# Spar7_rebuild.net
KiCad netlist of a schematic drawn in EAGLE
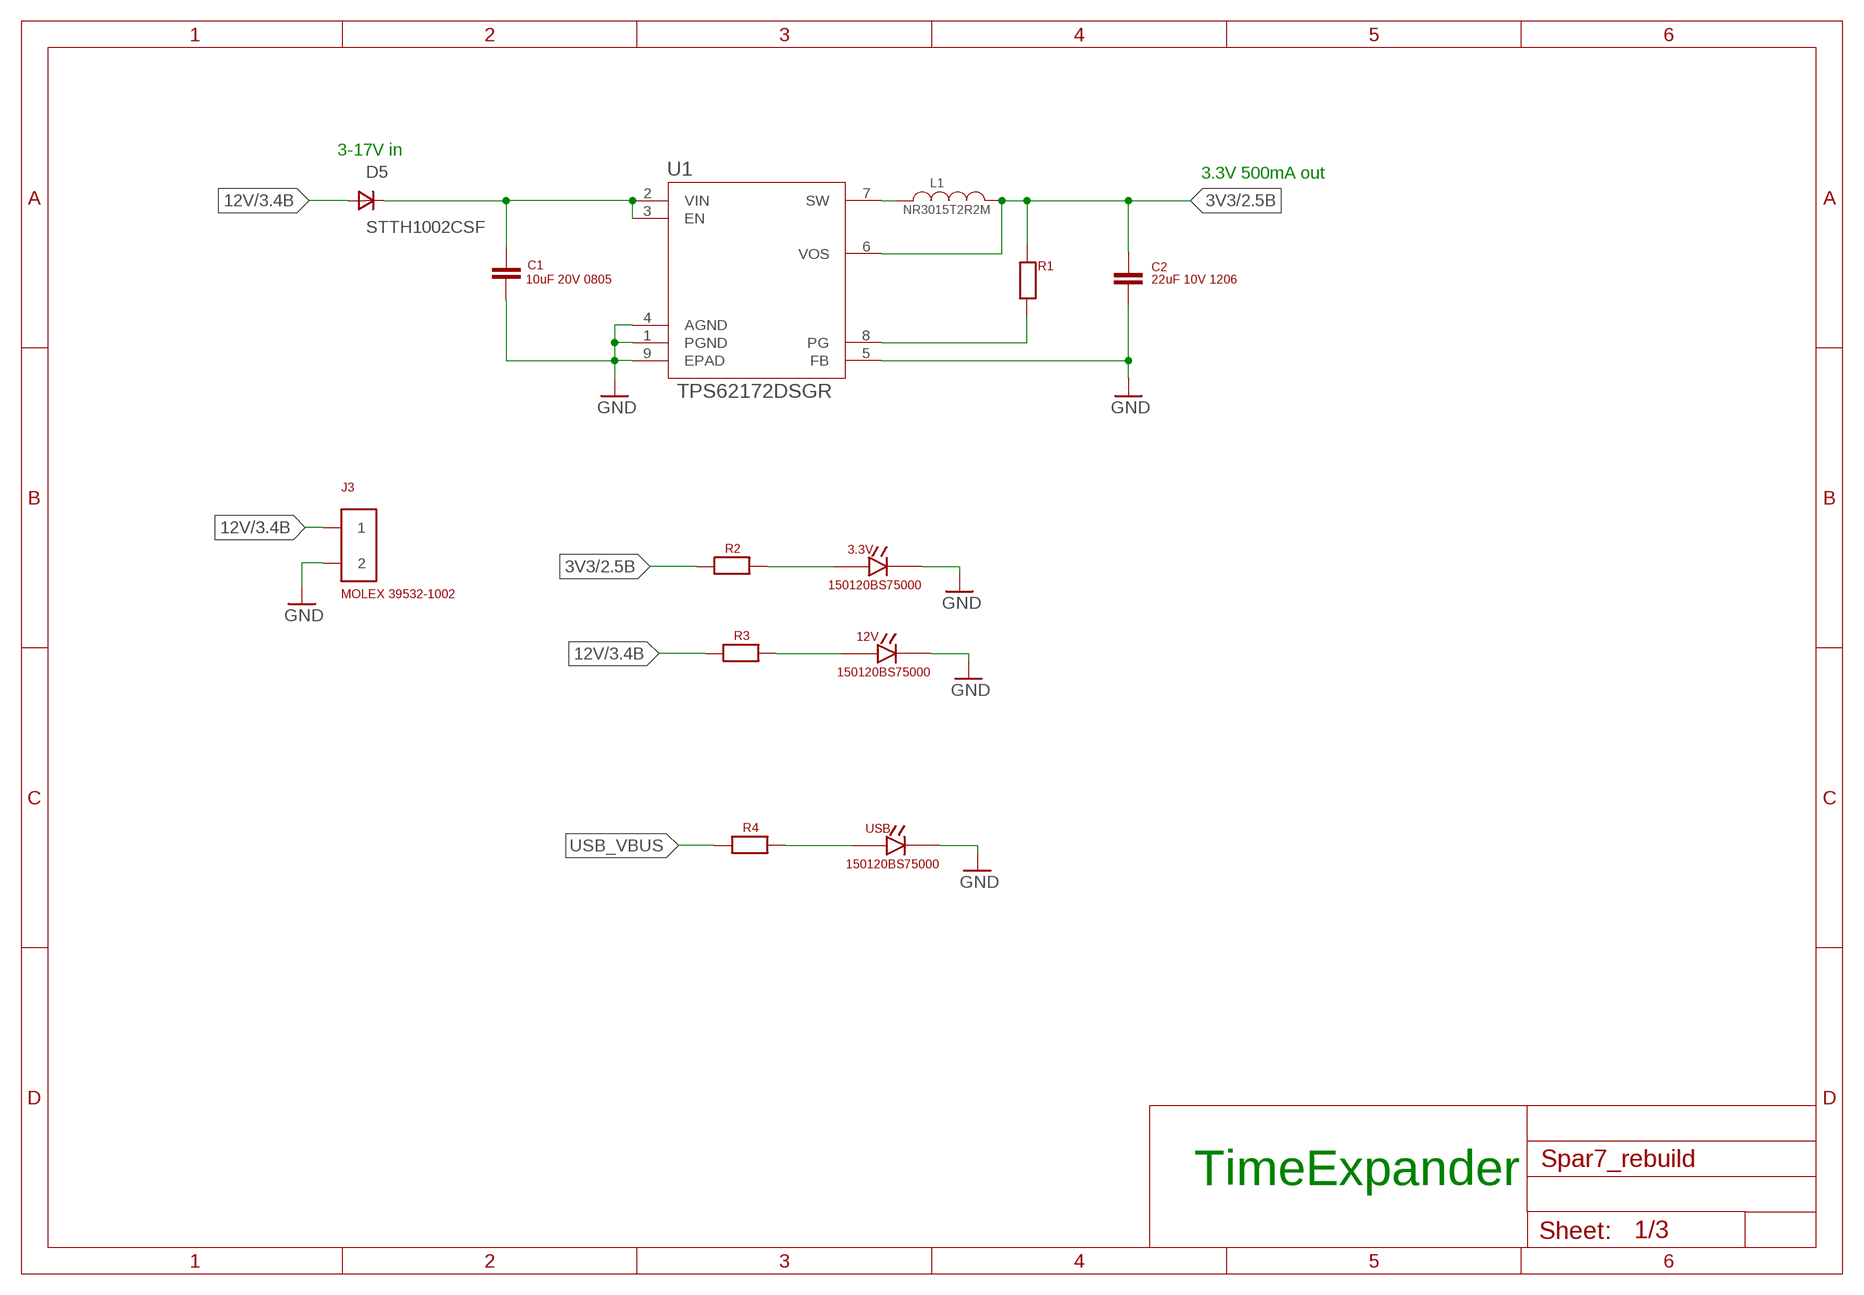
[diagram p0: schematic, sheet 1]
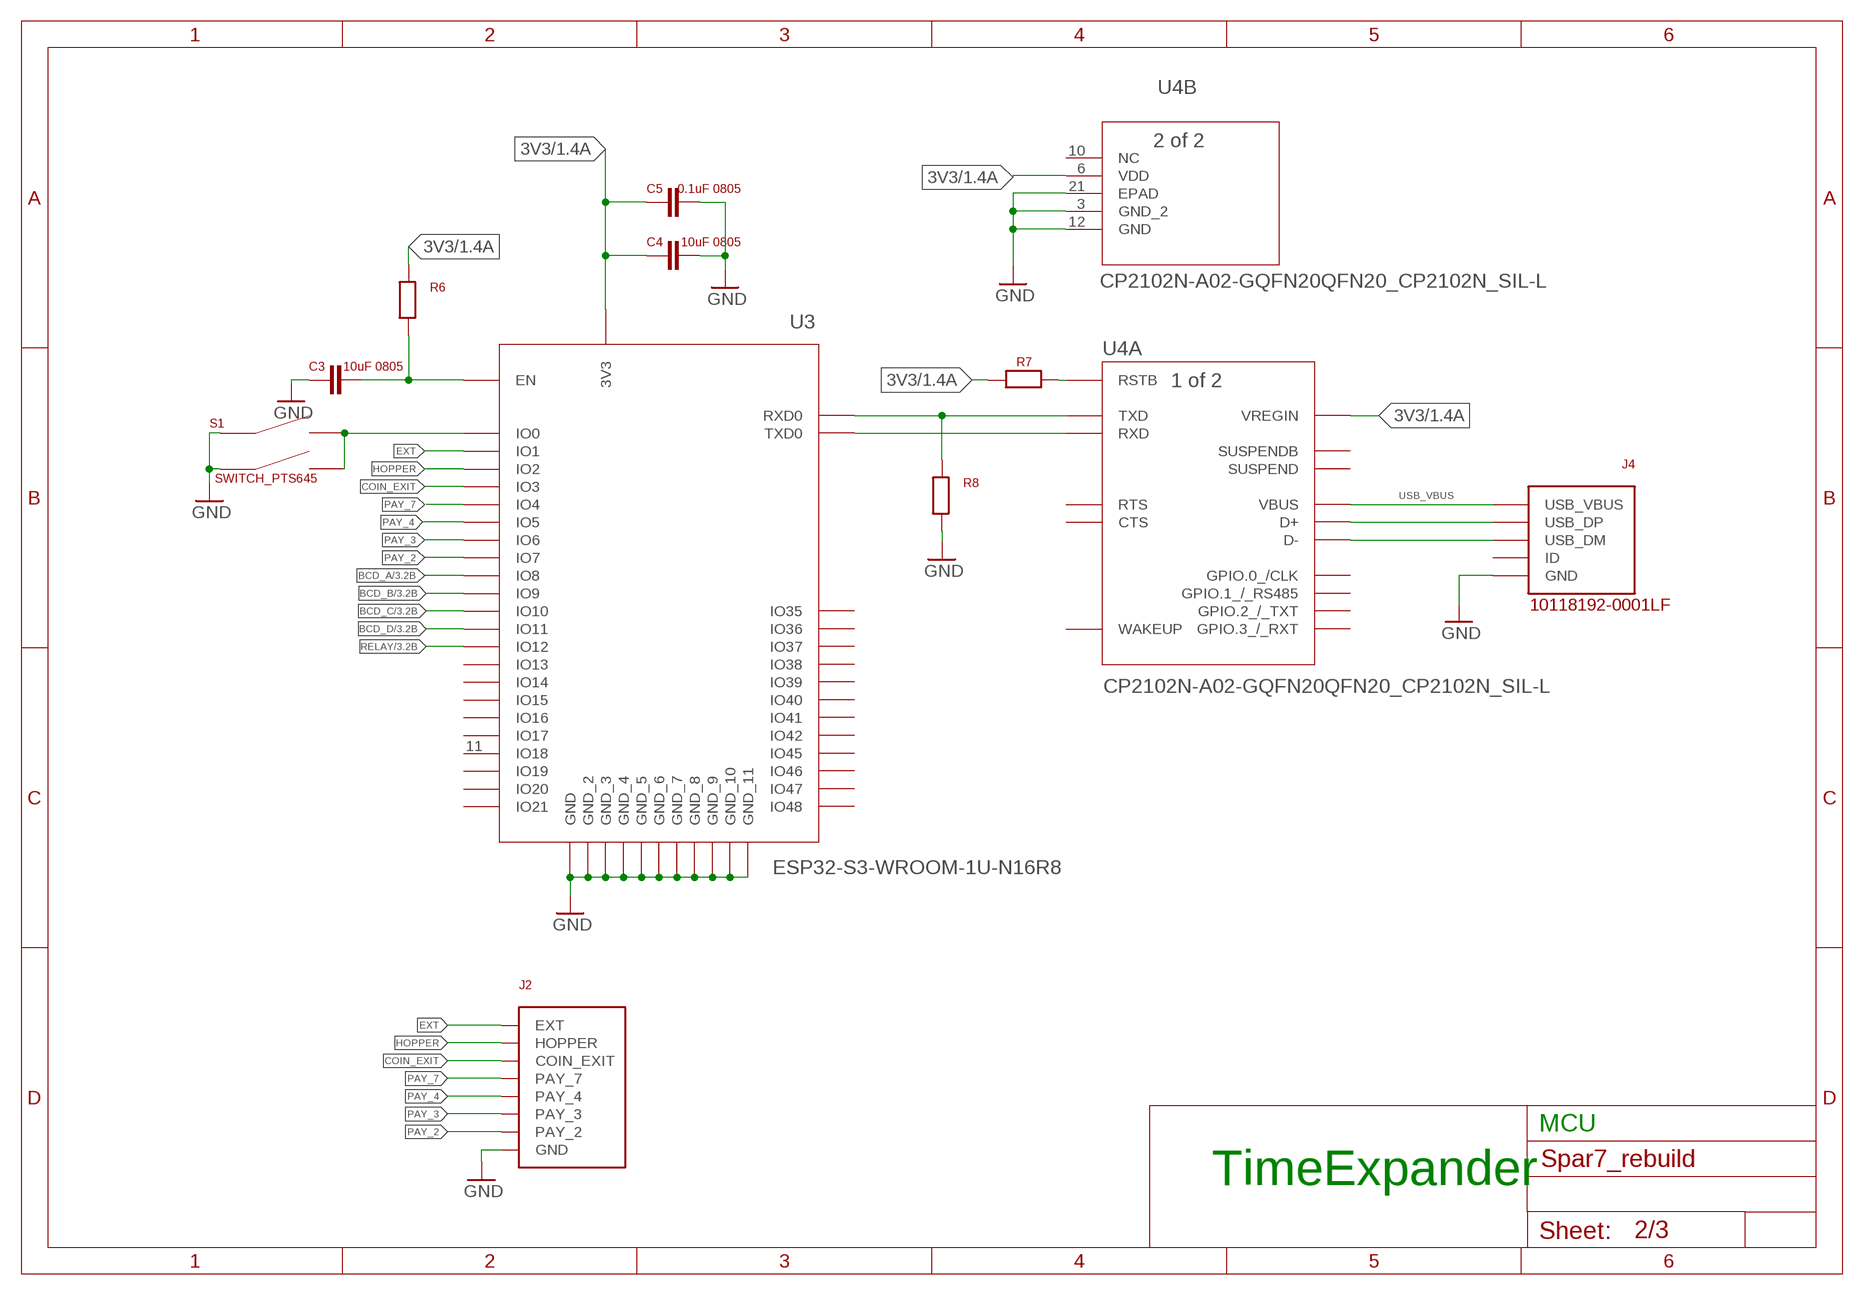
[diagram p1: schematic, sheet 2]
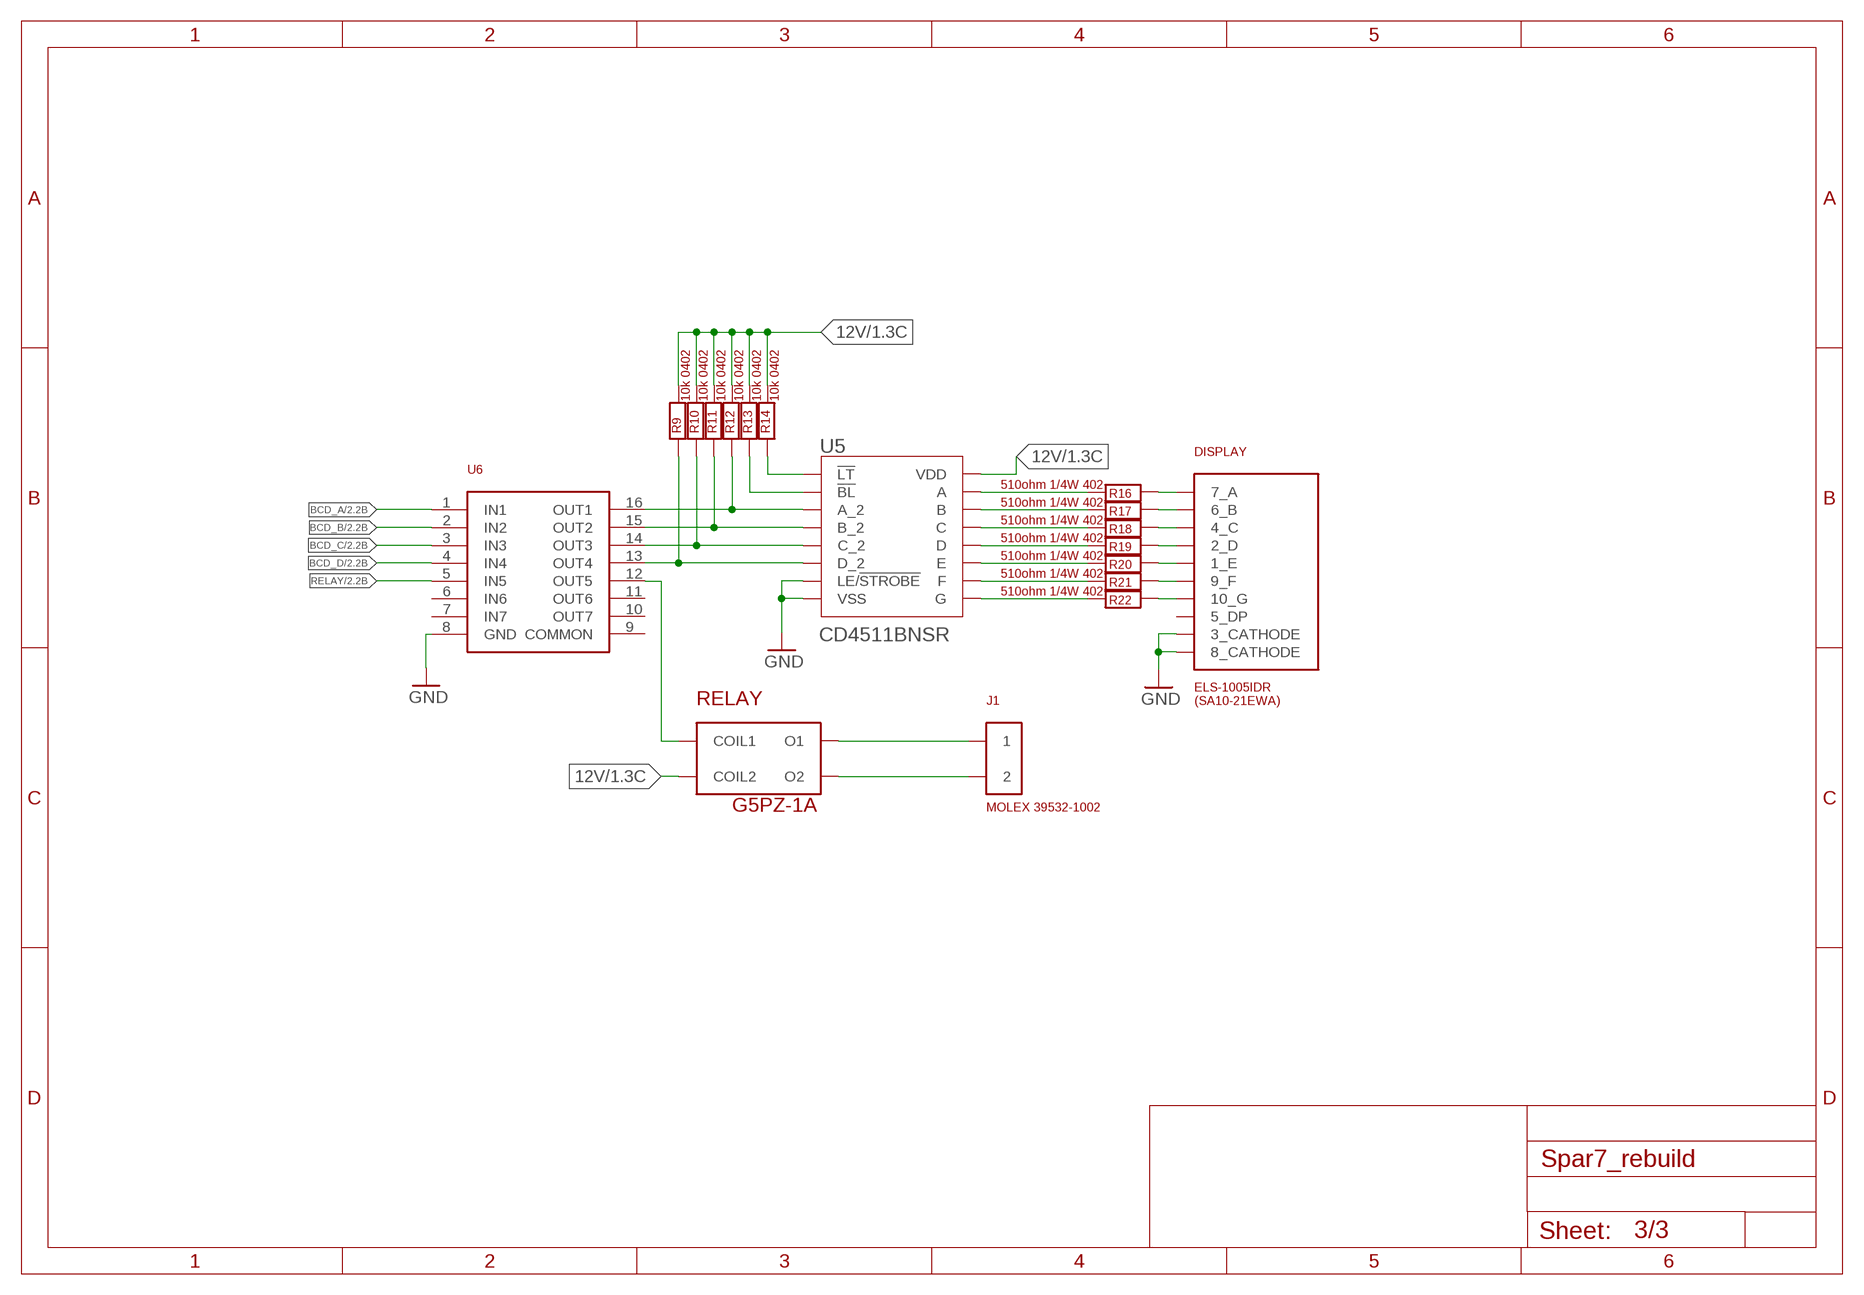
[diagram p2: schematic, sheet 3]

(export (version "E")
  (design (tool "Eeschema 10.0.6"))
  (components
    (comp (ref "DISPLAY")
      (value "ELS-1005IDR-SA10-21EWA")
      (footprint "eagle-import:ELS-1005IDR-SA10-21EWA")
      (libsource (lib "eagle-import") (part "ELS-1005IDR-SA10-21EWA"))
    )
    (comp (ref "J1")
      (value "MOLEX-39532-1002")
      (footprint "eagle-import:MOLEX-39532-1002")
      (libsource (lib "eagle-import") (part "MOLEX-39532-1002"))
    )
    (comp (ref "R9")
      (value "10k 0402")
      (footprint "eagle-import:RES_0402")
      (libsource (lib "eagle-import") (part "RESISTOR0402"))
    )
    (comp (ref "R10")
      (value "10k 0402")
      (footprint "eagle-import:RES_0402")
      (libsource (lib "eagle-import") (part "RESISTOR0402"))
    )
    (comp (ref "R11")
      (value "10k 0402")
      (footprint "eagle-import:RES_0402")
      (libsource (lib "eagle-import") (part "RESISTOR0402"))
    )
    (comp (ref "R12")
      (value "10k 0402")
      (footprint "eagle-import:RES_0402")
      (libsource (lib "eagle-import") (part "RESISTOR0402"))
    )
    (comp (ref "R13")
      (value "10k 0402")
      (footprint "eagle-import:RES_0402")
      (libsource (lib "eagle-import") (part "RESISTOR0402"))
    )
    (comp (ref "R14")
      (value "10k 0402")
      (footprint "eagle-import:RES_0402")
      (libsource (lib "eagle-import") (part "RESISTOR0402"))
    )
    (comp (ref "R16")
      (value "510ohm 1/4W 402")
      (footprint "eagle-import:RES_0402")
      (libsource (lib "eagle-import") (part "RESISTOR0402"))
    )
    (comp (ref "R17")
      (value "510ohm 1/4W 402")
      (footprint "eagle-import:RES_0402")
      (libsource (lib "eagle-import") (part "RESISTOR0402"))
    )
    (comp (ref "R18")
      (value "510ohm 1/4W 402")
      (footprint "eagle-import:RES_0402")
      (libsource (lib "eagle-import") (part "RESISTOR0402"))
    )
    (comp (ref "R19")
      (value "510ohm 1/4W 402")
      (footprint "eagle-import:RES_0402")
      (libsource (lib "eagle-import") (part "RESISTOR0402"))
    )
    (comp (ref "R20")
      (value "510ohm 1/4W 402")
      (footprint "eagle-import:RES_0402")
      (libsource (lib "eagle-import") (part "RESISTOR0402"))
    )
    (comp (ref "R21")
      (value "510ohm 1/4W 402")
      (footprint "eagle-import:RES_0402")
      (libsource (lib "eagle-import") (part "RESISTOR0402"))
    )
    (comp (ref "R22")
      (value "510ohm 1/4W 402")
      (footprint "eagle-import:RES_0402")
      (libsource (lib "eagle-import") (part "RESISTOR0402"))
    )
    (comp (ref "RELAY")
      (value "G5PZ-1A_RELAY")
      (footprint "eagle-import:G5PZ-1A_RELAY")
      (libsource (lib "eagle-import") (part "G5PZ-1A_RELAY"))
    )
    (comp (ref "U5")
      (value "CD4511BNSR")
      (footprint "eagle-import:NS16")
      (fields (field (name "COPYRIGHT") "Copyright (C) 2023 Ultra Librarian. All rights reserved."))
      (libsource (lib "eagle-import") (part "CD4511BNSR"))
    )
    (comp (ref "U6")
      (value "ULN2003D1013TR")
      (footprint "eagle-import:SO16-NARROW")
      (libsource (lib "eagle-import") (part "ULN2003D1013TR"))
    )
    (comp (ref "C3")
      (value "10uF 0805")
      (footprint "eagle-import:CAP_0805")
      (libsource (lib "eagle-import") (part "CAPACITOR0805"))
    )
    (comp (ref "C4")
      (value "10uF 0805")
      (footprint "eagle-import:CAP_0805")
      (libsource (lib "eagle-import") (part "CAPACITOR0805"))
    )
    (comp (ref "C5")
      (value "0.1uF 0805")
      (footprint "eagle-import:CAP_0805")
      (libsource (lib "eagle-import") (part "CAPACITOR0805"))
    )
    (comp (ref "J2")
      (value "SPAR7_REWIRED_TERM_BLOCK")
      (footprint "eagle-import:SPAR7_REWIRED_TERM_BLOCK")
      (libsource (lib "eagle-import") (part "SPAR7_REWIRED_TERM_BLOCK"))
    )
    (comp (ref "J4")
      (value "10118192-0001LF")
      (footprint "eagle-import:USB_RCPT_10118192-0001LF")
      (libsource (lib "eagle-import") (part "USB_RCPT_10118192-0001LF"))
    )
    (comp (ref "R6")
      (value "RESISTOR0402")
      (footprint "eagle-import:RES_0402")
      (libsource (lib "eagle-import") (part "RESISTOR0402"))
    )
    (comp (ref "R7")
      (value "RESISTOR0402")
      (footprint "eagle-import:RES_0402")
      (libsource (lib "eagle-import") (part "RESISTOR0402"))
    )
    (comp (ref "R8")
      (value "RESISTOR0402")
      (footprint "eagle-import:RES_0402")
      (libsource (lib "eagle-import") (part "RESISTOR0402"))
    )
    (comp (ref "S1")
      (value "SWITCH_PTS645")
      (footprint "eagle-import:SWITCH_PTS645_EE_NBIOT_01")
      (libsource (lib "eagle-import") (part "SWITCH_PTS645"))
    )
    (comp (ref "U3")
      (value "ESP32-S3-WROOM-1U-N16R8")
      (footprint "eagle-import:ESP32­S3­WROOM­1U_EXP")
      (fields (field (name "COPYRIGHT") "Copyright (C) 2023 Ultra Librarian. All rights reserved."))
      (libsource (lib "eagle-import") (part "ESP32-S3-WROOM-1U-N16R8"))
    )
    (comp (ref "U4")
      (value "CP2102N-A02-GQFN20QFN20_CP2102N_SIL-L")
      (footprint "eagle-import:QFN20_CP2102N_SIL-L")
      (fields
        (field (name "MANUFACTURER_PART_NUMBER") "CP2102N-A02-GQFN20")
        (field (name "COPYRIGHT") "Copyright (C) 2023 Ultra Librarian. All rights reserved.")
      )
      (libsource (lib "eagle-import") (part "CP2102N-A02-GQFN20QFN20_CP2102N_SIL-L"))
    )
    (comp (ref "3.3V")
      (value "150120BS75000")
      (footprint "eagle-import:150120BS75000")
      (libsource (lib "eagle-import") (part "LED150120BS75000"))
    )
    (comp (ref "12V")
      (value "150120BS75000")
      (footprint "eagle-import:150120BS75000")
      (libsource (lib "eagle-import") (part "LED150120BS75000"))
    )
    (comp (ref "C1")
      (value "10uF 20V 0805")
      (footprint "eagle-import:CAP_0805")
      (libsource (lib "eagle-import") (part "CAPACITOR0805"))
    )
    (comp (ref "C2")
      (value "22uF 10V 1206")
      (footprint "eagle-import:CAP_1206")
      (libsource (lib "eagle-import") (part "CAPACITOR1206"))
    )
    (comp (ref "D5")
      (value "STTH1002CSF")
      (footprint "eagle-import:DIODE_STTH1002CSF")
      (libsource (lib "eagle-import") (part "DIODESTTH1002CSF"))
    )
    (comp (ref "J3")
      (value "MOLEX-39532-1002")
      (footprint "eagle-import:MOLEX-39532-1002")
      (libsource (lib "eagle-import") (part "MOLEX-39532-1002"))
    )
    (comp (ref "L1")
      (value "NR3015T2R2M")
      (footprint "eagle-import:IND_TAIYO_NR3015_TAY")
      (libsource (lib "eagle-import") (part "NR3015T2R2M"))
    )
    (comp (ref "R1")
      (value "RESISTOR0402")
      (footprint "eagle-import:RES_0402")
      (libsource (lib "eagle-import") (part "RESISTOR0402"))
    )
    (comp (ref "R2")
      (value "RESISTOR0402")
      (footprint "eagle-import:RES_0402")
      (libsource (lib "eagle-import") (part "RESISTOR0402"))
    )
    (comp (ref "R3")
      (value "RESISTOR0402")
      (footprint "eagle-import:RES_0402")
      (libsource (lib "eagle-import") (part "RESISTOR0402"))
    )
    (comp (ref "R4")
      (value "RESISTOR0402")
      (footprint "eagle-import:RES_0402")
      (libsource (lib "eagle-import") (part "RESISTOR0402"))
    )
    (comp (ref "U1")
      (value "TPS62172DSGR")
      (footprint "eagle-import:DSG8_1P6X0P9")
      (fields
        (field (name "GENERIC_PART_NUMBER") "TPS62173")
        (field (name "MANUFACTURER") "Texas Instruments")
        (field (name "MANUFACTURER_PART_NUMBER") "TPS62173DSGR")
      )
      (libsource (lib "eagle-import") (part "TPS62173DSGR"))
    )
    (comp (ref "USB")
      (value "150120BS75000")
      (footprint "eagle-import:150120BS75000")
      (libsource (lib "eagle-import") (part "LED150120BS75000"))
    )
  )
  (nets
    (net (code "1") (name "3V3") (class "Default")
      (node (ref "C2") (pin "P$1") (pinfunction "1_P$1") (pintype "passive"))
      (node (ref "C4") (pin "P$1") (pinfunction "1_P$1") (pintype "passive"))
      (node (ref "C5") (pin "P$1") (pinfunction "1_P$1") (pintype "passive"))
      (node (ref "L1") (pin "1") (pinfunction "1_1") (pintype "passive"))
      (node (ref "R1") (pin "P$1") (pinfunction "P$1_P$1") (pintype "bidirectional"))
      (node (ref "R2") (pin "P$1") (pinfunction "P$1_P$1") (pintype "bidirectional"))
      (node (ref "R6") (pin "P$2") (pinfunction "P$2_P$2") (pintype "bidirectional"))
      (node (ref "R7") (pin "P$1") (pinfunction "P$1_P$1") (pintype "bidirectional"))
      (node (ref "U1") (pin "6") (pinfunction "VOS_6") (pintype "input"))
      (node (ref "U3") (pin "2") (pinfunction "3V3_2") (pintype "power_in"))
      (node (ref "U4") (pin "6") (pinfunction "VDD_6") (pintype "power_in"))
      (node (ref "U4") (pin "7") (pinfunction "VREGIN_7") (pintype "passive"))
    )
    (net (code "2") (name "12V") (class "Default")
      (node (ref "D5") (pin "A1") (pinfunction "A_A1") (pintype "passive"))
      (node (ref "D5") (pin "A2") (pinfunction "A_A2") (pintype "passive"))
      (node (ref "J3") (pin "1") (pinfunction "1_1") (pintype "power_in"))
      (node (ref "R10") (pin "P$2") (pinfunction "P$2_P$2") (pintype "bidirectional"))
      (node (ref "R11") (pin "P$2") (pinfunction "P$2_P$2") (pintype "bidirectional"))
      (node (ref "R12") (pin "P$2") (pinfunction "P$2_P$2") (pintype "bidirectional"))
      (node (ref "R13") (pin "P$2") (pinfunction "P$2_P$2") (pintype "bidirectional"))
      (node (ref "R14") (pin "P$2") (pinfunction "P$2_P$2") (pintype "bidirectional"))
      (node (ref "R3") (pin "P$1") (pinfunction "P$1_P$1") (pintype "bidirectional"))
      (node (ref "R9") (pin "P$2") (pinfunction "P$2_P$2") (pintype "bidirectional"))
      (node (ref "RELAY") (pin "COIL2") (pinfunction "COIL2_COIL2") (pintype "power_in"))
      (node (ref "U5") (pin "16") (pinfunction "VDD_16") (pintype "power_in"))
    )
    (net (code "3") (name "BCD_A") (class "Default")
      (node (ref "U3") (pin "12") (pinfunction "IO8_12") (pintype "bidirectional"))
      (node (ref "U6") (pin "1") (pinfunction "IN1_1") (pintype "bidirectional"))
    )
    (net (code "4") (name "BCD_B") (class "Default")
      (node (ref "U3") (pin "17") (pinfunction "IO9_17") (pintype "bidirectional"))
      (node (ref "U6") (pin "2") (pinfunction "IN2_2") (pintype "bidirectional"))
    )
    (net (code "5") (name "BCD_C") (class "Default")
      (node (ref "U3") (pin "18") (pinfunction "IO10_18") (pintype "bidirectional"))
      (node (ref "U6") (pin "3") (pinfunction "IN3_3") (pintype "bidirectional"))
    )
    (net (code "6") (name "BCD_D") (class "Default")
      (node (ref "U3") (pin "19") (pinfunction "IO11_19") (pintype "bidirectional"))
      (node (ref "U6") (pin "4") (pinfunction "IN4_4") (pintype "bidirectional"))
    )
    (net (code "7") (name "COIN_EXIT") (class "Default")
      (node (ref "J2") (pin "COIN_EXIT") (pinfunction "COIN_EXIT_COIN_EXIT") (pintype "power_in"))
      (node (ref "U3") (pin "15") (pinfunction "IO3_15") (pintype "bidirectional"))
    )
    (net (code "8") (name "EXT") (class "Default")
      (node (ref "J2") (pin "EXT") (pinfunction "EXT_EXT") (pintype "power_in"))
      (node (ref "U3") (pin "39") (pinfunction "IO1_39") (pintype "bidirectional"))
    )
    (net (code "9") (name "GND") (class "Default")
      (node (ref "12V") (pin "C") (pinfunction "C_C") (pintype "passive"))
      (node (ref "3.3V") (pin "C") (pinfunction "C_C") (pintype "passive"))
      (node (ref "C1") (pin "P$2") (pinfunction "2_P$2") (pintype "passive"))
      (node (ref "C2") (pin "P$2") (pinfunction "2_P$2") (pintype "passive"))
      (node (ref "C3") (pin "P$1") (pinfunction "1_P$1") (pintype "passive"))
      (node (ref "C4") (pin "P$2") (pinfunction "2_P$2") (pintype "passive"))
      (node (ref "C5") (pin "P$2") (pinfunction "2_P$2") (pintype "passive"))
      (node (ref "DISPLAY") (pin "3_CATHODE") (pinfunction "3_CATHODE_3_CATHODE") (pintype "bidirectional"))
      (node (ref "DISPLAY") (pin "8_CATHODE") (pinfunction "8_CATHODE_8_CATHODE") (pintype "bidirectional"))
      (node (ref "J2") (pin "GND") (pinfunction "GND_GND") (pintype "power_in"))
      (node (ref "J3") (pin "2") (pinfunction "2_2") (pintype "power_in"))
      (node (ref "J4") (pin "GND") (pinfunction "GND_GND") (pintype "passive"))
      (node (ref "R8") (pin "P$1") (pinfunction "P$1_P$1") (pintype "bidirectional"))
      (node (ref "S1") (pin "A1") (pinfunction "A1_A1") (pintype "bidirectional"))
      (node (ref "S1") (pin "A2") (pinfunction "A2_A2") (pintype "bidirectional"))
      (node (ref "U1") (pin "1") (pinfunction "PGND_1") (pintype "power_in"))
      (node (ref "U1") (pin "4") (pinfunction "AGND_4") (pintype "power_in"))
      (node (ref "U1") (pin "5") (pinfunction "FB_5") (pintype "input"))
      (node (ref "U1") (pin "9") (pinfunction "EPAD_9") (pintype "input"))
      (node (ref "U3") (pin "1") (pinfunction "GND_2_1") (pintype "passive"))
      (node (ref "U3") (pin "40") (pinfunction "GND_3_40") (pintype "passive"))
      (node (ref "U3") (pin "41") (pinfunction "GND_4_41") (pintype "passive"))
      (node (ref "U3") (pin "42") (pinfunction "GND_5_42") (pintype "passive"))
      (node (ref "U3") (pin "43") (pinfunction "GND_6_43") (pintype "passive"))
      (node (ref "U3") (pin "44") (pinfunction "GND_7_44") (pintype "passive"))
      (node (ref "U3") (pin "45") (pinfunction "GND_8_45") (pintype "passive"))
      (node (ref "U3") (pin "46") (pinfunction "GND_9_46") (pintype "passive"))
      (node (ref "U3") (pin "47") (pinfunction "GND_10_47") (pintype "passive"))
      (node (ref "U3") (pin "48") (pinfunction "GND_11_48") (pintype "passive"))
      (node (ref "U3") (pin "49") (pinfunction "GND_49") (pintype "passive"))
      (node (ref "U4") (pin "12") (pinfunction "GND_12") (pintype "passive"))
      (node (ref "U4") (pin "21") (pinfunction "EPAD_21") (pintype "passive"))
      (node (ref "U4") (pin "3") (pinfunction "GND_2_3") (pintype "passive"))
      (node (ref "U5") (pin "5") (pinfunction "LE/~{STROBE}_5") (pintype "passive"))
      (node (ref "U5") (pin "8") (pinfunction "VSS_8") (pintype "power_in"))
      (node (ref "U6") (pin "8") (pinfunction "GND_8") (pintype "bidirectional"))
      (node (ref "USB") (pin "C") (pinfunction "C_C") (pintype "passive"))
    )
    (net (code "10") (name "HOPPER") (class "Default")
      (node (ref "J2") (pin "HOPPER") (pinfunction "HOPPER_HOPPER") (pintype "power_in"))
      (node (ref "U3") (pin "38") (pinfunction "IO2_38") (pintype "bidirectional"))
    )
    (net (code "11") (name "Net-(3.3V-PadA)") (class "Default")
      (node (ref "3.3V") (pin "A") (pinfunction "A_A") (pintype "passive"))
      (node (ref "R2") (pin "P$2") (pinfunction "P$2_P$2") (pintype "bidirectional"))
    )
    (net (code "12") (name "Net-(12V-PadA)") (class "Default")
      (node (ref "12V") (pin "A") (pinfunction "A_A") (pintype "passive"))
      (node (ref "R3") (pin "P$2") (pinfunction "P$2_P$2") (pintype "bidirectional"))
    )
    (net (code "13") (name "Net-(C1-1)") (class "Default")
      (node (ref "C1") (pin "P$1") (pinfunction "1_P$1") (pintype "passive"))
      (node (ref "D5") (pin "C") (pinfunction "C_C") (pintype "passive"))
      (node (ref "U1") (pin "2") (pinfunction "VIN_2") (pintype "input"))
      (node (ref "U1") (pin "3") (pinfunction "EN_3") (pintype "input"))
    )
    (net (code "14") (name "Net-(C3-2)") (class "Default")
      (node (ref "C3") (pin "P$2") (pinfunction "2_P$2") (pintype "passive"))
      (node (ref "R6") (pin "P$1") (pinfunction "P$1_P$1") (pintype "bidirectional"))
      (node (ref "U3") (pin "3") (pinfunction "EN_3") (pintype "input"))
    )
    (net (code "15") (name "Net-(DISPLAY-Pad1_E)") (class "Default")
      (node (ref "DISPLAY") (pin "1_E") (pinfunction "1_E_1_E") (pintype "bidirectional"))
      (node (ref "R20") (pin "P$1") (pinfunction "P$1_P$1") (pintype "bidirectional"))
    )
    (net (code "16") (name "Net-(DISPLAY-Pad2_D)") (class "Default")
      (node (ref "DISPLAY") (pin "2_D") (pinfunction "2_D_2_D") (pintype "bidirectional"))
      (node (ref "R19") (pin "P$1") (pinfunction "P$1_P$1") (pintype "bidirectional"))
    )
    (net (code "17") (name "Net-(DISPLAY-Pad4_C)") (class "Default")
      (node (ref "DISPLAY") (pin "4_C") (pinfunction "4_C_4_C") (pintype "bidirectional"))
      (node (ref "R18") (pin "P$1") (pinfunction "P$1_P$1") (pintype "bidirectional"))
    )
    (net (code "18") (name "Net-(DISPLAY-Pad6_B)") (class "Default")
      (node (ref "DISPLAY") (pin "6_B") (pinfunction "6_B_6_B") (pintype "bidirectional"))
      (node (ref "R17") (pin "P$1") (pinfunction "P$1_P$1") (pintype "bidirectional"))
    )
    (net (code "19") (name "Net-(DISPLAY-Pad7_A)") (class "Default")
      (node (ref "DISPLAY") (pin "7_A") (pinfunction "7_A_7_A") (pintype "bidirectional"))
      (node (ref "R16") (pin "P$1") (pinfunction "P$1_P$1") (pintype "bidirectional"))
    )
    (net (code "20") (name "Net-(DISPLAY-Pad9_F)") (class "Default")
      (node (ref "DISPLAY") (pin "9_F") (pinfunction "9_F_9_F") (pintype "bidirectional"))
      (node (ref "R21") (pin "P$1") (pinfunction "P$1_P$1") (pintype "bidirectional"))
    )
    (net (code "21") (name "Net-(DISPLAY-Pad10_G)") (class "Default")
      (node (ref "DISPLAY") (pin "10_G") (pinfunction "10_G_10_G") (pintype "bidirectional"))
      (node (ref "R22") (pin "P$1") (pinfunction "P$1_P$1") (pintype "bidirectional"))
    )
    (net (code "22") (name "Net-(J1-Pad1)") (class "Default")
      (node (ref "J1") (pin "1") (pinfunction "1_1") (pintype "power_in"))
      (node (ref "RELAY") (pin "O1") (pinfunction "O1_O1") (pintype "power_in"))
    )
    (net (code "23") (name "Net-(J1-Pad2)") (class "Default")
      (node (ref "J1") (pin "2") (pinfunction "2_2") (pintype "power_in"))
      (node (ref "RELAY") (pin "O2") (pinfunction "O2_O2") (pintype "power_in"))
    )
    (net (code "24") (name "Net-(J4-USB_DM)") (class "Default")
      (node (ref "J4") (pin "D-") (pinfunction "USB_DM_D-") (pintype "passive"))
      (node (ref "U4") (pin "5") (pinfunction "D-_5") (pintype "passive"))
    )
    (net (code "25") (name "Net-(J4-USB_DP)") (class "Default")
      (node (ref "J4") (pin "D+") (pinfunction "USB_DP_D+") (pintype "passive"))
      (node (ref "U4") (pin "4") (pinfunction "D+_4") (pintype "passive"))
    )
    (net (code "26") (name "Net-(R4-PadP$2)") (class "Default")
      (node (ref "R4") (pin "P$2") (pinfunction "P$2_P$2") (pintype "bidirectional"))
      (node (ref "USB") (pin "A") (pinfunction "A_A") (pintype "passive"))
    )
    (net (code "27") (name "Net-(U1-PG)") (class "Default")
      (node (ref "R1") (pin "P$2") (pinfunction "P$2_P$2") (pintype "bidirectional"))
      (node (ref "U1") (pin "8") (pinfunction "PG_8") (pintype "input"))
    )
    (net (code "28") (name "Net-(U1-SW)") (class "Default")
      (node (ref "L1") (pin "2") (pinfunction "2_2") (pintype "passive"))
      (node (ref "U1") (pin "7") (pinfunction "SW_7") (pintype "output"))
    )
    (net (code "29") (name "Net-(U3-IO0)") (class "Default")
      (node (ref "S1") (pin "B1") (pinfunction "B1_B1") (pintype "bidirectional"))
      (node (ref "S1") (pin "B2") (pinfunction "B2_B2") (pintype "bidirectional"))
      (node (ref "U3") (pin "27") (pinfunction "IO0_27") (pintype "bidirectional"))
    )
    (net (code "30") (name "Net-(U3-RXD0)") (class "Default")
      (node (ref "R8") (pin "P$2") (pinfunction "P$2_P$2") (pintype "bidirectional"))
      (node (ref "U3") (pin "36") (pinfunction "RXD0_36") (pintype "bidirectional"))
      (node (ref "U4") (pin "18") (pinfunction "TXD_18") (pintype "passive"))
    )
    (net (code "31") (name "Net-(U3-TXD0)") (class "Default")
      (node (ref "U3") (pin "37") (pinfunction "TXD0_37") (pintype "bidirectional"))
      (node (ref "U4") (pin "17") (pinfunction "RXD_17") (pintype "passive"))
    )
    (net (code "32") (name "Net-(U4A-RSTB)") (class "Default")
      (node (ref "R7") (pin "P$2") (pinfunction "P$2_P$2") (pintype "bidirectional"))
      (node (ref "U4") (pin "9") (pinfunction "RSTB_9") (pintype "passive"))
    )
    (net (code "33") (name "Net-(U5-A)") (class "Default")
      (node (ref "R16") (pin "P$2") (pinfunction "P$2_P$2") (pintype "bidirectional"))
      (node (ref "U5") (pin "13") (pinfunction "A_13") (pintype "passive"))
    )
    (net (code "34") (name "Net-(U5-A_2)") (class "Default")
      (node (ref "R12") (pin "P$1") (pinfunction "P$1_P$1") (pintype "bidirectional"))
      (node (ref "U5") (pin "7") (pinfunction "A_2_7") (pintype "passive"))
      (node (ref "U6") (pin "16") (pinfunction "OUT1_16") (pintype "bidirectional"))
    )
    (net (code "35") (name "Net-(U5-B)") (class "Default")
      (node (ref "R17") (pin "P$2") (pinfunction "P$2_P$2") (pintype "bidirectional"))
      (node (ref "U5") (pin "12") (pinfunction "B_12") (pintype "passive"))
    )
    (net (code "36") (name "Net-(U5-B_2)") (class "Default")
      (node (ref "R11") (pin "P$1") (pinfunction "P$1_P$1") (pintype "bidirectional"))
      (node (ref "U5") (pin "1") (pinfunction "B_2_1") (pintype "passive"))
      (node (ref "U6") (pin "15") (pinfunction "OUT2_15") (pintype "bidirectional"))
    )
    (net (code "37") (name "Net-(U5-C)") (class "Default")
      (node (ref "R18") (pin "P$2") (pinfunction "P$2_P$2") (pintype "bidirectional"))
      (node (ref "U5") (pin "11") (pinfunction "C_11") (pintype "passive"))
    )
    (net (code "38") (name "Net-(U5-C_2)") (class "Default")
      (node (ref "R10") (pin "P$1") (pinfunction "P$1_P$1") (pintype "bidirectional"))
      (node (ref "U5") (pin "2") (pinfunction "C_2_2") (pintype "passive"))
      (node (ref "U6") (pin "14") (pinfunction "OUT3_14") (pintype "bidirectional"))
    )
    (net (code "39") (name "Net-(U5-D)") (class "Default")
      (node (ref "R19") (pin "P$2") (pinfunction "P$2_P$2") (pintype "bidirectional"))
      (node (ref "U5") (pin "10") (pinfunction "D_10") (pintype "passive"))
    )
    (net (code "40") (name "Net-(U5-D_2)") (class "Default")
      (node (ref "R9") (pin "P$1") (pinfunction "P$1_P$1") (pintype "bidirectional"))
      (node (ref "U5") (pin "6") (pinfunction "D_2_6") (pintype "passive"))
      (node (ref "U6") (pin "13") (pinfunction "OUT4_13") (pintype "bidirectional"))
    )
    (net (code "41") (name "Net-(U5-E)") (class "Default")
      (node (ref "R20") (pin "P$2") (pinfunction "P$2_P$2") (pintype "bidirectional"))
      (node (ref "U5") (pin "9") (pinfunction "E_9") (pintype "passive"))
    )
    (net (code "42") (name "Net-(U5-F)") (class "Default")
      (node (ref "R21") (pin "P$2") (pinfunction "P$2_P$2") (pintype "bidirectional"))
      (node (ref "U5") (pin "15") (pinfunction "F_15") (pintype "passive"))
    )
    (net (code "43") (name "Net-(U5-G)") (class "Default")
      (node (ref "R22") (pin "P$2") (pinfunction "P$2_P$2") (pintype "bidirectional"))
      (node (ref "U5") (pin "14") (pinfunction "G_14") (pintype "passive"))
    )
    (net (code "44") (name "Net-(U5-~{BL})") (class "Default")
      (node (ref "R13") (pin "P$1") (pinfunction "P$1_P$1") (pintype "bidirectional"))
      (node (ref "U5") (pin "4") (pinfunction "~{BL}_4") (pintype "passive"))
    )
    (net (code "45") (name "Net-(U5-~{LT})") (class "Default")
      (node (ref "R14") (pin "P$1") (pinfunction "P$1_P$1") (pintype "bidirectional"))
      (node (ref "U5") (pin "3") (pinfunction "~{LT}_3") (pintype "passive"))
    )
    (net (code "46") (name "Net-(U6-OUT5)") (class "Default")
      (node (ref "RELAY") (pin "COIL1") (pinfunction "COIL1_COIL1") (pintype "power_in"))
      (node (ref "U6") (pin "12") (pinfunction "OUT5_12") (pintype "bidirectional"))
    )
    (net (code "47") (name "PAY_2") (class "Default")
      (node (ref "J2") (pin "PAY_2") (pinfunction "PAY_2_PAY_2") (pintype "power_in"))
      (node (ref "U3") (pin "7") (pinfunction "IO7_7") (pintype "bidirectional"))
    )
    (net (code "48") (name "PAY_3") (class "Default")
      (node (ref "J2") (pin "PAY_3") (pinfunction "PAY_3_PAY_3") (pintype "power_in"))
      (node (ref "U3") (pin "6") (pinfunction "IO6_6") (pintype "bidirectional"))
    )
    (net (code "49") (name "PAY_4") (class "Default")
      (node (ref "J2") (pin "PAY_4") (pinfunction "PAY_4_PAY_4") (pintype "power_in"))
      (node (ref "U3") (pin "5") (pinfunction "IO5_5") (pintype "bidirectional"))
    )
    (net (code "50") (name "PAY_7") (class "Default")
      (node (ref "J2") (pin "PAY_7") (pinfunction "PAY_7_PAY_7") (pintype "power_in"))
      (node (ref "U3") (pin "4") (pinfunction "IO4_4") (pintype "bidirectional"))
    )
    (net (code "51") (name "RELAY") (class "Default")
      (node (ref "U3") (pin "20") (pinfunction "IO12_20") (pintype "bidirectional"))
      (node (ref "U6") (pin "5") (pinfunction "IN5_5") (pintype "bidirectional"))
    )
    (net (code "52") (name "USB_VBUS") (class "Default")
      (node (ref "J4") (pin "VCC") (pinfunction "USB_VBUS_VCC") (pintype "passive"))
      (node (ref "R4") (pin "P$1") (pinfunction "P$1_P$1") (pintype "bidirectional"))
      (node (ref "U4") (pin "8") (pinfunction "VBUS_8") (pintype "passive"))
    )
    (net (code "53") (name "unconnected-(DISPLAY-Pad5_DP)") (class "Default")
      (node (ref "DISPLAY") (pin "5_DP") (pinfunction "5_DP_5_DP") (pintype "bidirectional"))
    )
    (net (code "54") (name "unconnected-(J4-PadID)") (class "Default")
      (node (ref "J4") (pin "ID") (pinfunction "ID_ID") (pintype "passive"))
    )
    (net (code "55") (name "unconnected-(U3-IO13-Pad21)") (class "Default")
      (node (ref "U3") (pin "21") (pinfunction "IO13_21") (pintype "bidirectional"))
    )
    (net (code "56") (name "unconnected-(U3-IO14-Pad22)") (class "Default")
      (node (ref "U3") (pin "22") (pinfunction "IO14_22") (pintype "bidirectional"))
    )
    (net (code "57") (name "unconnected-(U3-IO15-Pad8)") (class "Default")
      (node (ref "U3") (pin "8") (pinfunction "IO15_8") (pintype "bidirectional"))
    )
    (net (code "58") (name "unconnected-(U3-IO16-Pad9)") (class "Default")
      (node (ref "U3") (pin "9") (pinfunction "IO16_9") (pintype "bidirectional"))
    )
    (net (code "59") (name "unconnected-(U3-IO17-Pad10)") (class "Default")
      (node (ref "U3") (pin "10") (pinfunction "IO17_10") (pintype "bidirectional"))
    )
    (net (code "60") (name "unconnected-(U3-IO18-Pad11)") (class "Default")
      (node (ref "U3") (pin "11") (pinfunction "IO18_11") (pintype "bidirectional"))
    )
    (net (code "61") (name "unconnected-(U3-IO19-Pad13)") (class "Default")
      (node (ref "U3") (pin "13") (pinfunction "IO19_13") (pintype "bidirectional"))
    )
    (net (code "62") (name "unconnected-(U3-IO20-Pad14)") (class "Default")
      (node (ref "U3") (pin "14") (pinfunction "IO20_14") (pintype "bidirectional"))
    )
    (net (code "63") (name "unconnected-(U3-IO21-Pad23)") (class "Default")
      (node (ref "U3") (pin "23") (pinfunction "IO21_23") (pintype "bidirectional"))
    )
    (net (code "64") (name "unconnected-(U3-IO35-Pad28)") (class "Default")
      (node (ref "U3") (pin "28") (pinfunction "IO35_28") (pintype "bidirectional"))
    )
    (net (code "65") (name "unconnected-(U3-IO36-Pad29)") (class "Default")
      (node (ref "U3") (pin "29") (pinfunction "IO36_29") (pintype "bidirectional"))
    )
    (net (code "66") (name "unconnected-(U3-IO37-Pad30)") (class "Default")
      (node (ref "U3") (pin "30") (pinfunction "IO37_30") (pintype "bidirectional"))
    )
    (net (code "67") (name "unconnected-(U3-IO38-Pad31)") (class "Default")
      (node (ref "U3") (pin "31") (pinfunction "IO38_31") (pintype "bidirectional"))
    )
    (net (code "68") (name "unconnected-(U3-IO39-Pad32)") (class "Default")
      (node (ref "U3") (pin "32") (pinfunction "IO39_32") (pintype "bidirectional"))
    )
    (net (code "69") (name "unconnected-(U3-IO40-Pad33)") (class "Default")
      (node (ref "U3") (pin "33") (pinfunction "IO40_33") (pintype "bidirectional"))
    )
    (net (code "70") (name "unconnected-(U3-IO41-Pad34)") (class "Default")
      (node (ref "U3") (pin "34") (pinfunction "IO41_34") (pintype "bidirectional"))
    )
    (net (code "71") (name "unconnected-(U3-IO42-Pad35)") (class "Default")
      (node (ref "U3") (pin "35") (pinfunction "IO42_35") (pintype "bidirectional"))
    )
    (net (code "72") (name "unconnected-(U3-IO45-Pad26)") (class "Default")
      (node (ref "U3") (pin "26") (pinfunction "IO45_26") (pintype "bidirectional"))
    )
    (net (code "73") (name "unconnected-(U3-IO46-Pad16)") (class "Default")
      (node (ref "U3") (pin "16") (pinfunction "IO46_16") (pintype "bidirectional"))
    )
    (net (code "74") (name "unconnected-(U3-IO47-Pad24)") (class "Default")
      (node (ref "U3") (pin "24") (pinfunction "IO47_24") (pintype "bidirectional"))
    )
    (net (code "75") (name "unconnected-(U3-IO48-Pad25)") (class "Default")
      (node (ref "U3") (pin "25") (pinfunction "IO48_25") (pintype "bidirectional"))
    )
    (net (code "76") (name "unconnected-(U4A-CTS-Pad15)") (class "Default")
      (node (ref "U4") (pin "15") (pinfunction "CTS_15") (pintype "passive"))
    )
    (net (code "77") (name "unconnected-(U4A-GPIO.0_{slash}CLK-Pad2)") (class "Default")
      (node (ref "U4") (pin "2") (pinfunction "GPIO.0_/CLK_2") (pintype "bidirectional"))
    )
    (net (code "78") (name "unconnected-(U4A-GPIO.1_{slash}_RS485-Pad1)") (class "Default")
      (node (ref "U4") (pin "1") (pinfunction "GPIO.1_/_RS485_1") (pintype "bidirectional"))
    )
    (net (code "79") (name "unconnected-(U4A-GPIO.2_{slash}_TXT-Pad20)") (class "Default")
      (node (ref "U4") (pin "20") (pinfunction "GPIO.2_/_TXT_20") (pintype "bidirectional"))
    )
    (net (code "80") (name "unconnected-(U4A-GPIO.3_{slash}_RXT-Pad19)") (class "Default")
      (node (ref "U4") (pin "19") (pinfunction "GPIO.3_/_RXT_19") (pintype "bidirectional"))
    )
    (net (code "81") (name "unconnected-(U4A-RTS-Pad16)") (class "Default")
      (node (ref "U4") (pin "16") (pinfunction "RTS_16") (pintype "passive"))
    )
    (net (code "82") (name "unconnected-(U4A-SUSPEND-Pad14)") (class "Default")
      (node (ref "U4") (pin "14") (pinfunction "SUSPEND_14") (pintype "passive"))
    )
    (net (code "83") (name "unconnected-(U4A-SUSPENDB-Pad11)") (class "Default")
      (node (ref "U4") (pin "11") (pinfunction "SUSPENDB_11") (pintype "passive"))
    )
    (net (code "84") (name "unconnected-(U4A-WAKEUP-Pad13)") (class "Default")
      (node (ref "U4") (pin "13") (pinfunction "WAKEUP_13") (pintype "passive"))
    )
    (net (code "85") (name "unconnected-(U4B-NC-Pad10)") (class "Default")
      (node (ref "U4") (pin "10") (pinfunction "NC_10") (pintype "no_connect"))
    )
    (net (code "86") (name "unconnected-(U6-COMMON-Pad9)") (class "Default")
      (node (ref "U6") (pin "9") (pinfunction "COMMON_9") (pintype "bidirectional"))
    )
    (net (code "87") (name "unconnected-(U6-IN6-Pad6)") (class "Default")
      (node (ref "U6") (pin "6") (pinfunction "IN6_6") (pintype "bidirectional"))
    )
    (net (code "88") (name "unconnected-(U6-IN7-Pad7)") (class "Default")
      (node (ref "U6") (pin "7") (pinfunction "IN7_7") (pintype "bidirectional"))
    )
    (net (code "89") (name "unconnected-(U6-OUT6-Pad11)") (class "Default")
      (node (ref "U6") (pin "11") (pinfunction "OUT6_11") (pintype "bidirectional"))
    )
    (net (code "90") (name "unconnected-(U6-OUT7-Pad10)") (class "Default")
      (node (ref "U6") (pin "10") (pinfunction "OUT7_10") (pintype "bidirectional"))
    )
  )
)
